# SCH_release-af_2024-07-28.net
KiCad netlist of a schematic drawn in EasyEDA
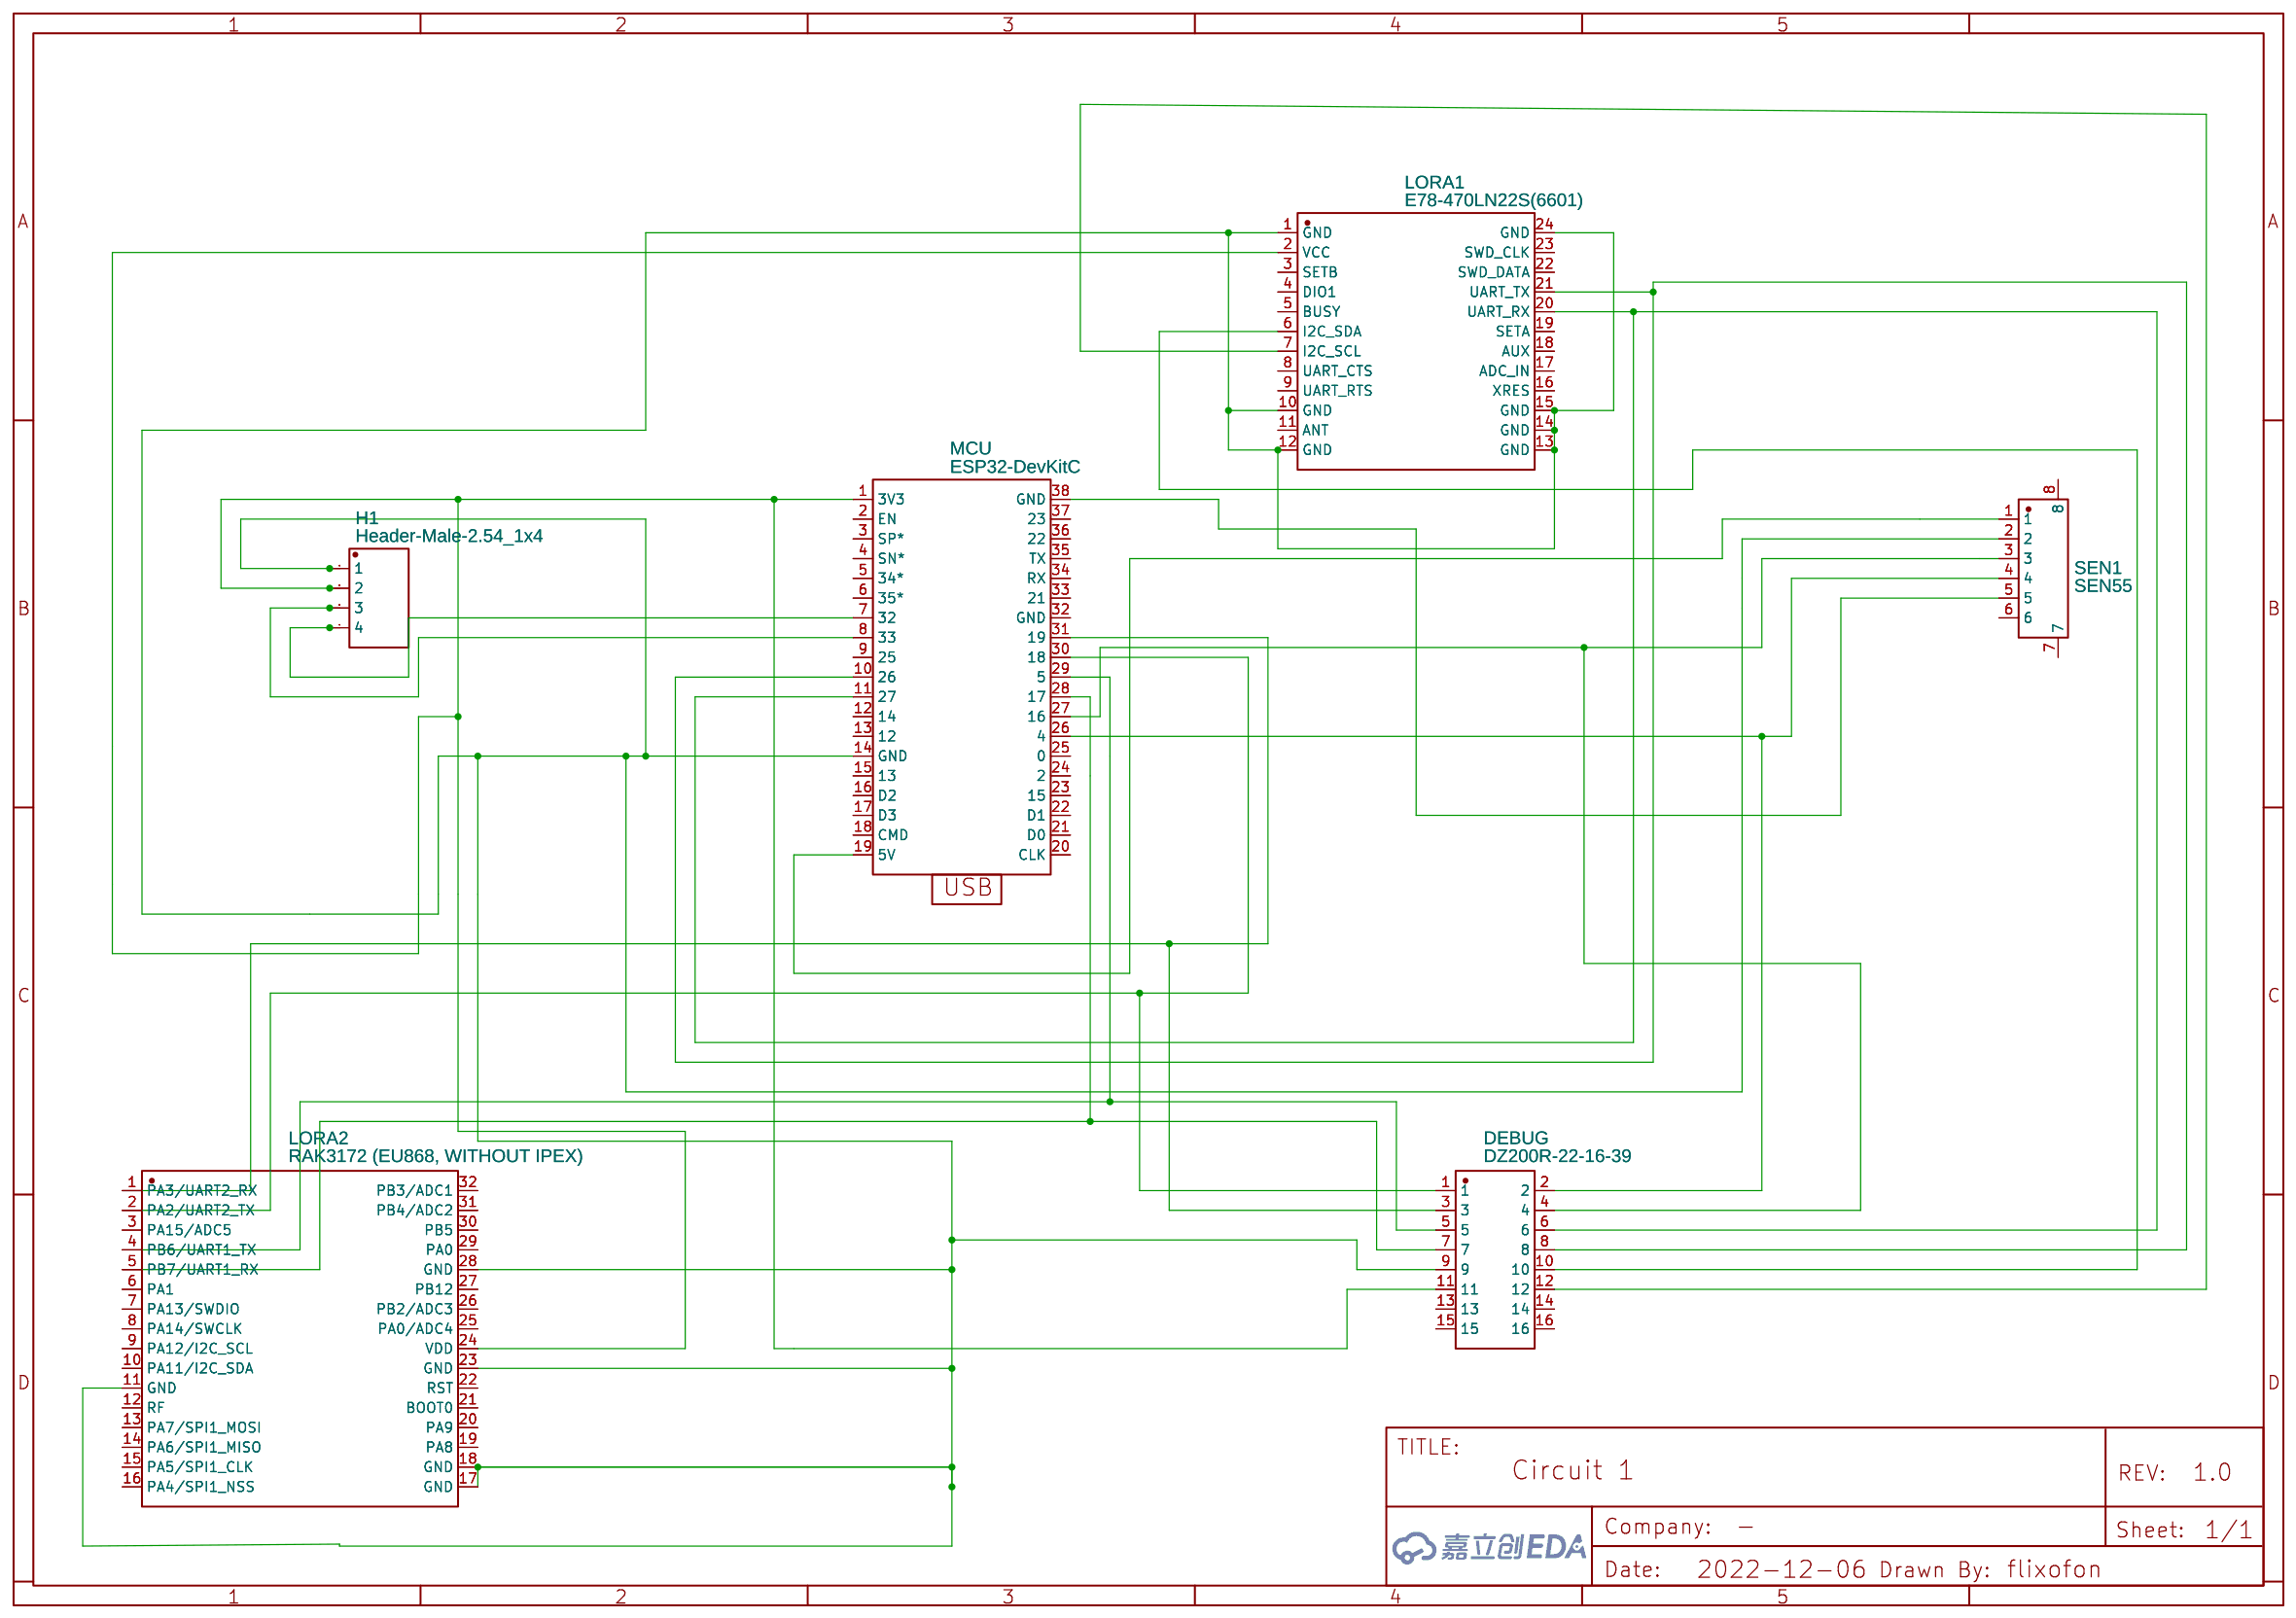
[diagram p0: schematic sheet]

(export (version "E")
  (design (tool "Eeschema 10.0.6"))
  (components
    (comp (ref "DEBUG")
      (value "DZ200R-22-16-39")
      (fields (field (name "Manufacturer") "DEALON(德艺隆)"))
      (libsource (lib "") (part "DZ200R-22-16-39"))
    )
    (comp (ref "H1")
      (value "Header-Male-2.54_1x4")
      (fields (field (name "Manufacturer Part") "B-2100S04P-A110") (field (name "Manufacturer") "Ckmtw(灿科盟)"))
      (libsource (lib "") (part "Header-Male-2.54_1x4"))
    )
    (comp (ref "LORA1")
      (value "E78-470LN22S(6601)")
      (fields (field (name "Manufacturer") "EBYTE(亿佰特)"))
      (libsource (lib "") (part "E78-470LN22S(6601)"))
    )
    (comp (ref "LORA2")
      (value "RAK3172 (EU868, WITHOUT IPEX)")
      (fields (field (name "Manufacturer Part") "RAK3172 (EU868, without IPEX)"))
      (libsource (lib "") (part "RAK3172 (EU868, WITHOUT IPEX)"))
    )
    (comp (ref "MCU")
      (value "ESP32-DevKitC")
      (fields (field (name "Manufacturer") "32U WROOM"))
      (libsource (lib "") (part "ESP32-AZ-Delivery-DevkitC-V4"))
    )
    (comp (ref "SEN1")
      (value "SEN55")
      (fields (field (name "Manufacturer Part") "532610671") (field (name "Manufacturer") "MOLEX"))
      (libsource (lib "") (part "53261-0671"))
    )
  )
  (nets
    (net (code "1") (name "Net-(DEBUG-Pad9)") (class "Default")
      (node (ref "DEBUG") (pin "9") (pinfunction "9_9") (pintype "unspecified"))
      (node (ref "H1") (pin "1") (pinfunction "1_1") (pintype "unspecified"))
      (node (ref "LORA1") (pin "1") (pinfunction "GND_1") (pintype "unspecified"))
      (node (ref "LORA1") (pin "10") (pinfunction "GND_10") (pintype "unspecified"))
      (node (ref "LORA1") (pin "12") (pinfunction "GND_12") (pintype "unspecified"))
      (node (ref "LORA1") (pin "13") (pinfunction "GND_13") (pintype "unspecified"))
      (node (ref "LORA1") (pin "14") (pinfunction "GND_14") (pintype "unspecified"))
      (node (ref "LORA1") (pin "15") (pinfunction "GND_15") (pintype "unspecified"))
      (node (ref "LORA1") (pin "24") (pinfunction "GND_24") (pintype "unspecified"))
      (node (ref "LORA2") (pin "11") (pinfunction "GND_11") (pintype "unspecified"))
      (node (ref "LORA2") (pin "17") (pinfunction "GND_17") (pintype "unspecified"))
      (node (ref "LORA2") (pin "18") (pinfunction "GND_18") (pintype "unspecified"))
      (node (ref "LORA2") (pin "23") (pinfunction "GND_23") (pintype "unspecified"))
      (node (ref "LORA2") (pin "28") (pinfunction "GND_28") (pintype "unspecified"))
      (node (ref "MCU") (pin "14") (pinfunction "GND_14") (pintype "unspecified"))
      (node (ref "SEN1") (pin "2") (pinfunction "2_2") (pintype "unspecified"))
    )
    (net (code "2") (name "Net-(LORA1-I2C_SCL)") (class "Default")
      (node (ref "DEBUG") (pin "12") (pinfunction "12_12") (pintype "unspecified"))
      (node (ref "LORA1") (pin "7") (pinfunction "I2C_SCL_7") (pintype "unspecified"))
    )
    (net (code "3") (name "Net-(LORA1-I2C_SDA)") (class "Default")
      (node (ref "DEBUG") (pin "10") (pinfunction "10_10") (pintype "unspecified"))
      (node (ref "LORA1") (pin "6") (pinfunction "I2C_SDA_6") (pintype "unspecified"))
    )
    (net (code "4") (name "Net-(LORA1-UART_RX)") (class "Default")
      (node (ref "DEBUG") (pin "6") (pinfunction "6_6") (pintype "unspecified"))
      (node (ref "LORA1") (pin "20") (pinfunction "UART_RX_20") (pintype "unspecified"))
      (node (ref "MCU") (pin "11") (pinfunction "27_11") (pintype "unspecified"))
    )
    (net (code "5") (name "Net-(LORA1-UART_TX)") (class "Default")
      (node (ref "DEBUG") (pin "8") (pinfunction "8_8") (pintype "unspecified"))
      (node (ref "LORA1") (pin "21") (pinfunction "UART_TX_21") (pintype "unspecified"))
      (node (ref "MCU") (pin "10") (pinfunction "26_10") (pintype "unspecified"))
    )
    (net (code "6") (name "Net-(LORA1-VCC)") (class "Default")
      (node (ref "DEBUG") (pin "11") (pinfunction "11_11") (pintype "unspecified"))
      (node (ref "H1") (pin "2") (pinfunction "2_2") (pintype "unspecified"))
      (node (ref "LORA1") (pin "2") (pinfunction "VCC_2") (pintype "unspecified"))
      (node (ref "LORA2") (pin "24") (pinfunction "VDD_24") (pintype "unspecified"))
      (node (ref "MCU") (pin "1") (pinfunction "3V3_1") (pintype "unspecified"))
    )
    (net (code "7") (name "Net-(LORA2-PA2{slash}UART2_TX)") (class "Default")
      (node (ref "DEBUG") (pin "1") (pinfunction "1_1") (pintype "unspecified"))
      (node (ref "LORA2") (pin "2") (pinfunction "PA2/UART2_TX_2") (pintype "unspecified"))
      (node (ref "MCU") (pin "30") (pinfunction "18_30") (pintype "unspecified"))
    )
    (net (code "8") (name "Net-(LORA2-PA3{slash}UART2_RX)") (class "Default")
      (node (ref "DEBUG") (pin "3") (pinfunction "3_3") (pintype "unspecified"))
      (node (ref "LORA2") (pin "1") (pinfunction "PA3/UART2_RX_1") (pintype "unspecified"))
      (node (ref "MCU") (pin "31") (pinfunction "19_31") (pintype "unspecified"))
    )
    (net (code "9") (name "Net-(LORA2-PB6{slash}UART1_TX)") (class "Default")
      (node (ref "DEBUG") (pin "5") (pinfunction "5_5") (pintype "unspecified"))
      (node (ref "LORA2") (pin "4") (pinfunction "PB6/UART1_TX_4") (pintype "unspecified"))
      (node (ref "MCU") (pin "29") (pinfunction "5_29") (pintype "unspecified"))
    )
    (net (code "10") (name "Net-(LORA2-PB7{slash}UART1_RX)") (class "Default")
      (node (ref "DEBUG") (pin "7") (pinfunction "7_7") (pintype "unspecified"))
      (node (ref "LORA2") (pin "5") (pinfunction "PB7/UART1_RX_5") (pintype "unspecified"))
      (node (ref "MCU") (pin "28") (pinfunction "17_28") (pintype "unspecified"))
    )
    (net (code "11") (name "Net-(MCU-4)") (class "Default")
      (node (ref "DEBUG") (pin "2") (pinfunction "2_2") (pintype "unspecified"))
      (node (ref "MCU") (pin "26") (pinfunction "4_26") (pintype "unspecified"))
      (node (ref "SEN1") (pin "4") (pinfunction "4_4") (pintype "unspecified"))
    )
    (net (code "12") (name "Net-(MCU-5V)") (class "Default")
      (node (ref "MCU") (pin "19") (pinfunction "5V_19") (pintype "unspecified"))
      (node (ref "SEN1") (pin "1") (pinfunction "1_1") (pintype "unspecified"))
    )
    (net (code "13") (name "Net-(MCU-16)") (class "Default")
      (node (ref "DEBUG") (pin "4") (pinfunction "4_4") (pintype "unspecified"))
      (node (ref "MCU") (pin "27") (pinfunction "16_27") (pintype "unspecified"))
      (node (ref "SEN1") (pin "3") (pinfunction "3_3") (pintype "unspecified"))
    )
    (net (code "14") (name "Net-(MCU-32)") (class "Default")
      (node (ref "H1") (pin "4") (pinfunction "4_4") (pintype "unspecified"))
      (node (ref "MCU") (pin "7") (pinfunction "32_7") (pintype "unspecified"))
    )
    (net (code "15") (name "Net-(MCU-33)") (class "Default")
      (node (ref "H1") (pin "3") (pinfunction "3_3") (pintype "unspecified"))
      (node (ref "MCU") (pin "8") (pinfunction "33_8") (pintype "unspecified"))
    )
    (net (code "16") (name "Net-(MCU-GND-Pad38)") (class "Default")
      (node (ref "MCU") (pin "38") (pinfunction "GND_38") (pintype "unspecified"))
      (node (ref "SEN1") (pin "5") (pinfunction "5_5") (pintype "unspecified"))
    )
    (net (code "17") (name "unconnected-(DEBUG-Pad13)") (class "Default")
      (node (ref "DEBUG") (pin "13") (pinfunction "13_13") (pintype "unspecified"))
    )
    (net (code "18") (name "unconnected-(DEBUG-Pad14)") (class "Default")
      (node (ref "DEBUG") (pin "14") (pinfunction "14_14") (pintype "unspecified"))
    )
    (net (code "19") (name "unconnected-(DEBUG-Pad15)") (class "Default")
      (node (ref "DEBUG") (pin "15") (pinfunction "15_15") (pintype "unspecified"))
    )
    (net (code "20") (name "unconnected-(DEBUG-Pad16)") (class "Default")
      (node (ref "DEBUG") (pin "16") (pinfunction "16_16") (pintype "unspecified"))
    )
    (net (code "21") (name "unconnected-(LORA1-ADC_IN-Pad17)") (class "Default")
      (node (ref "LORA1") (pin "17") (pinfunction "ADC_IN_17") (pintype "unspecified"))
    )
    (net (code "22") (name "unconnected-(LORA1-ANT-Pad11)") (class "Default")
      (node (ref "LORA1") (pin "11") (pinfunction "ANT_11") (pintype "unspecified"))
    )
    (net (code "23") (name "unconnected-(LORA1-AUX-Pad18)") (class "Default")
      (node (ref "LORA1") (pin "18") (pinfunction "AUX_18") (pintype "unspecified"))
    )
    (net (code "24") (name "unconnected-(LORA1-BUSY-Pad5)") (class "Default")
      (node (ref "LORA1") (pin "5") (pinfunction "BUSY_5") (pintype "unspecified"))
    )
    (net (code "25") (name "unconnected-(LORA1-DIO1-Pad4)") (class "Default")
      (node (ref "LORA1") (pin "4") (pinfunction "DIO1_4") (pintype "unspecified"))
    )
    (net (code "26") (name "unconnected-(LORA1-SETA-Pad19)") (class "Default")
      (node (ref "LORA1") (pin "19") (pinfunction "SETA_19") (pintype "unspecified"))
    )
    (net (code "27") (name "unconnected-(LORA1-SETB-Pad3)") (class "Default")
      (node (ref "LORA1") (pin "3") (pinfunction "SETB_3") (pintype "unspecified"))
    )
    (net (code "28") (name "unconnected-(LORA1-SWD_CLK-Pad23)") (class "Default")
      (node (ref "LORA1") (pin "23") (pinfunction "SWD_CLK_23") (pintype "unspecified"))
    )
    (net (code "29") (name "unconnected-(LORA1-SWD_DATA-Pad22)") (class "Default")
      (node (ref "LORA1") (pin "22") (pinfunction "SWD_DATA_22") (pintype "unspecified"))
    )
    (net (code "30") (name "unconnected-(LORA1-UART_CTS-Pad8)") (class "Default")
      (node (ref "LORA1") (pin "8") (pinfunction "UART_CTS_8") (pintype "unspecified"))
    )
    (net (code "31") (name "unconnected-(LORA1-UART_RTS-Pad9)") (class "Default")
      (node (ref "LORA1") (pin "9") (pinfunction "UART_RTS_9") (pintype "unspecified"))
    )
    (net (code "32") (name "unconnected-(LORA1-XRES-Pad16)") (class "Default")
      (node (ref "LORA1") (pin "16") (pinfunction "XRES_16") (pintype "unspecified"))
    )
    (net (code "33") (name "unconnected-(LORA2-BOOT0-Pad21)") (class "Default")
      (node (ref "LORA2") (pin "21") (pinfunction "BOOT0_21") (pintype "unspecified"))
    )
    (net (code "34") (name "unconnected-(LORA2-PA0-Pad29)") (class "Default")
      (node (ref "LORA2") (pin "29") (pinfunction "PA0_29") (pintype "unspecified"))
    )
    (net (code "35") (name "unconnected-(LORA2-PA0{slash}ADC4-Pad25)") (class "Default")
      (node (ref "LORA2") (pin "25") (pinfunction "PA0/ADC4_25") (pintype "unspecified"))
    )
    (net (code "36") (name "unconnected-(LORA2-PA1-Pad6)") (class "Default")
      (node (ref "LORA2") (pin "6") (pinfunction "PA1_6") (pintype "unspecified"))
    )
    (net (code "37") (name "unconnected-(LORA2-PA4{slash}SPI1_NSS-Pad16)") (class "Default")
      (node (ref "LORA2") (pin "16") (pinfunction "PA4/SPI1_NSS_16") (pintype "unspecified"))
    )
    (net (code "38") (name "unconnected-(LORA2-PA5{slash}SPI1_CLK-Pad15)") (class "Default")
      (node (ref "LORA2") (pin "15") (pinfunction "PA5/SPI1_CLK_15") (pintype "unspecified"))
    )
    (net (code "39") (name "unconnected-(LORA2-PA6{slash}SPI1_MISO-Pad14)") (class "Default")
      (node (ref "LORA2") (pin "14") (pinfunction "PA6/SPI1_MISO_14") (pintype "unspecified"))
    )
    (net (code "40") (name "unconnected-(LORA2-PA7{slash}SPI1_MOSI-Pad13)") (class "Default")
      (node (ref "LORA2") (pin "13") (pinfunction "PA7/SPI1_MOSI_13") (pintype "unspecified"))
    )
    (net (code "41") (name "unconnected-(LORA2-PA8-Pad19)") (class "Default")
      (node (ref "LORA2") (pin "19") (pinfunction "PA8_19") (pintype "unspecified"))
    )
    (net (code "42") (name "unconnected-(LORA2-PA9-Pad20)") (class "Default")
      (node (ref "LORA2") (pin "20") (pinfunction "PA9_20") (pintype "unspecified"))
    )
    (net (code "43") (name "unconnected-(LORA2-PA11{slash}I2C_SDA-Pad10)") (class "Default")
      (node (ref "LORA2") (pin "10") (pinfunction "PA11/I2C_SDA_10") (pintype "unspecified"))
    )
    (net (code "44") (name "unconnected-(LORA2-PA12{slash}I2C_SCL-Pad9)") (class "Default")
      (node (ref "LORA2") (pin "9") (pinfunction "PA12/I2C_SCL_9") (pintype "unspecified"))
    )
    (net (code "45") (name "unconnected-(LORA2-PA13{slash}SWDIO-Pad7)") (class "Default")
      (node (ref "LORA2") (pin "7") (pinfunction "PA13/SWDIO_7") (pintype "unspecified"))
    )
    (net (code "46") (name "unconnected-(LORA2-PA14{slash}SWCLK-Pad8)") (class "Default")
      (node (ref "LORA2") (pin "8") (pinfunction "PA14/SWCLK_8") (pintype "unspecified"))
    )
    (net (code "47") (name "unconnected-(LORA2-PA15{slash}ADC5-Pad3)") (class "Default")
      (node (ref "LORA2") (pin "3") (pinfunction "PA15/ADC5_3") (pintype "unspecified"))
    )
    (net (code "48") (name "unconnected-(LORA2-PB2{slash}ADC3-Pad26)") (class "Default")
      (node (ref "LORA2") (pin "26") (pinfunction "PB2/ADC3_26") (pintype "unspecified"))
    )
    (net (code "49") (name "unconnected-(LORA2-PB3{slash}ADC1-Pad32)") (class "Default")
      (node (ref "LORA2") (pin "32") (pinfunction "PB3/ADC1_32") (pintype "unspecified"))
    )
    (net (code "50") (name "unconnected-(LORA2-PB4{slash}ADC2-Pad31)") (class "Default")
      (node (ref "LORA2") (pin "31") (pinfunction "PB4/ADC2_31") (pintype "unspecified"))
    )
    (net (code "51") (name "unconnected-(LORA2-PB5-Pad30)") (class "Default")
      (node (ref "LORA2") (pin "30") (pinfunction "PB5_30") (pintype "unspecified"))
    )
    (net (code "52") (name "unconnected-(LORA2-PB12-Pad27)") (class "Default")
      (node (ref "LORA2") (pin "27") (pinfunction "PB12_27") (pintype "unspecified"))
    )
    (net (code "53") (name "unconnected-(LORA2-RF-Pad12)") (class "Default")
      (node (ref "LORA2") (pin "12") (pinfunction "RF_12") (pintype "unspecified"))
    )
    (net (code "54") (name "unconnected-(LORA2-RST-Pad22)") (class "Default")
      (node (ref "LORA2") (pin "22") (pinfunction "RST_22") (pintype "unspecified"))
    )
    (net (code "55") (name "unconnected-(MCU-0-Pad25)") (class "Default")
      (node (ref "MCU") (pin "25") (pinfunction "0_25") (pintype "unspecified"))
    )
    (net (code "56") (name "unconnected-(MCU-2-Pad24)") (class "Default")
      (node (ref "MCU") (pin "24") (pinfunction "2_24") (pintype "unspecified"))
    )
    (net (code "57") (name "unconnected-(MCU-12-Pad13)") (class "Default")
      (node (ref "MCU") (pin "13") (pinfunction "12_13") (pintype "unspecified"))
    )
    (net (code "58") (name "unconnected-(MCU-13-Pad15)") (class "Default")
      (node (ref "MCU") (pin "15") (pinfunction "13_15") (pintype "unspecified"))
    )
    (net (code "59") (name "unconnected-(MCU-14-Pad12)") (class "Default")
      (node (ref "MCU") (pin "12") (pinfunction "14_12") (pintype "unspecified"))
    )
    (net (code "60") (name "unconnected-(MCU-15-Pad23)") (class "Default")
      (node (ref "MCU") (pin "23") (pinfunction "15_23") (pintype "unspecified"))
    )
    (net (code "61") (name "unconnected-(MCU-21-Pad33)") (class "Default")
      (node (ref "MCU") (pin "33") (pinfunction "21_33") (pintype "unspecified"))
    )
    (net (code "62") (name "unconnected-(MCU-22-Pad36)") (class "Default")
      (node (ref "MCU") (pin "36") (pinfunction "22_36") (pintype "unspecified"))
    )
    (net (code "63") (name "unconnected-(MCU-23-Pad37)") (class "Default")
      (node (ref "MCU") (pin "37") (pinfunction "23_37") (pintype "unspecified"))
    )
    (net (code "64") (name "unconnected-(MCU-25-Pad9)") (class "Default")
      (node (ref "MCU") (pin "9") (pinfunction "25_9") (pintype "unspecified"))
    )
    (net (code "65") (name "unconnected-(MCU-34*-Pad5)") (class "Default")
      (node (ref "MCU") (pin "5") (pinfunction "34*_5") (pintype "unspecified"))
    )
    (net (code "66") (name "unconnected-(MCU-35*-Pad6)") (class "Default")
      (node (ref "MCU") (pin "6") (pinfunction "35*_6") (pintype "unspecified"))
    )
    (net (code "67") (name "unconnected-(MCU-CLK-Pad20)") (class "Default")
      (node (ref "MCU") (pin "20") (pinfunction "CLK_20") (pintype "unspecified"))
    )
    (net (code "68") (name "unconnected-(MCU-CMD-Pad18)") (class "Default")
      (node (ref "MCU") (pin "18") (pinfunction "CMD_18") (pintype "unspecified"))
    )
    (net (code "69") (name "unconnected-(MCU-D0-Pad21)") (class "Default")
      (node (ref "MCU") (pin "21") (pinfunction "D0_21") (pintype "unspecified"))
    )
    (net (code "70") (name "unconnected-(MCU-D1-Pad22)") (class "Default")
      (node (ref "MCU") (pin "22") (pinfunction "D1_22") (pintype "unspecified"))
    )
    (net (code "71") (name "unconnected-(MCU-D2-Pad16)") (class "Default")
      (node (ref "MCU") (pin "16") (pinfunction "D2_16") (pintype "unspecified"))
    )
    (net (code "72") (name "unconnected-(MCU-D3-Pad17)") (class "Default")
      (node (ref "MCU") (pin "17") (pinfunction "D3_17") (pintype "unspecified"))
    )
    (net (code "73") (name "unconnected-(MCU-EN-Pad2)") (class "Default")
      (node (ref "MCU") (pin "2") (pinfunction "EN_2") (pintype "unspecified"))
    )
    (net (code "74") (name "unconnected-(MCU-GND-Pad32)") (class "Default")
      (node (ref "MCU") (pin "32") (pinfunction "GND_32") (pintype "unspecified"))
    )
    (net (code "75") (name "unconnected-(MCU-RX-Pad34)") (class "Default")
      (node (ref "MCU") (pin "34") (pinfunction "RX_34") (pintype "unspecified"))
    )
    (net (code "76") (name "unconnected-(MCU-SN*-Pad4)") (class "Default")
      (node (ref "MCU") (pin "4") (pinfunction "SN*_4") (pintype "unspecified"))
    )
    (net (code "77") (name "unconnected-(MCU-SP*-Pad3)") (class "Default")
      (node (ref "MCU") (pin "3") (pinfunction "SP*_3") (pintype "unspecified"))
    )
    (net (code "78") (name "unconnected-(MCU-TX-Pad35)") (class "Default")
      (node (ref "MCU") (pin "35") (pinfunction "TX_35") (pintype "unspecified"))
    )
    (net (code "79") (name "unconnected-(SEN1-Pad6)") (class "Default")
      (node (ref "SEN1") (pin "6") (pinfunction "6_6") (pintype "unspecified"))
    )
    (net (code "80") (name "unconnected-(SEN1-Pad7)") (class "Default")
      (node (ref "SEN1") (pin "7") (pinfunction "7_7") (pintype "unspecified"))
    )
    (net (code "81") (name "unconnected-(SEN1-Pad8)") (class "Default")
      (node (ref "SEN1") (pin "8") (pinfunction "8_8") (pintype "unspecified"))
    )
  )
)
